# EdgeMax_ExtraMemory.net
KiCad netlist of a schematic drawn in Altium Designer
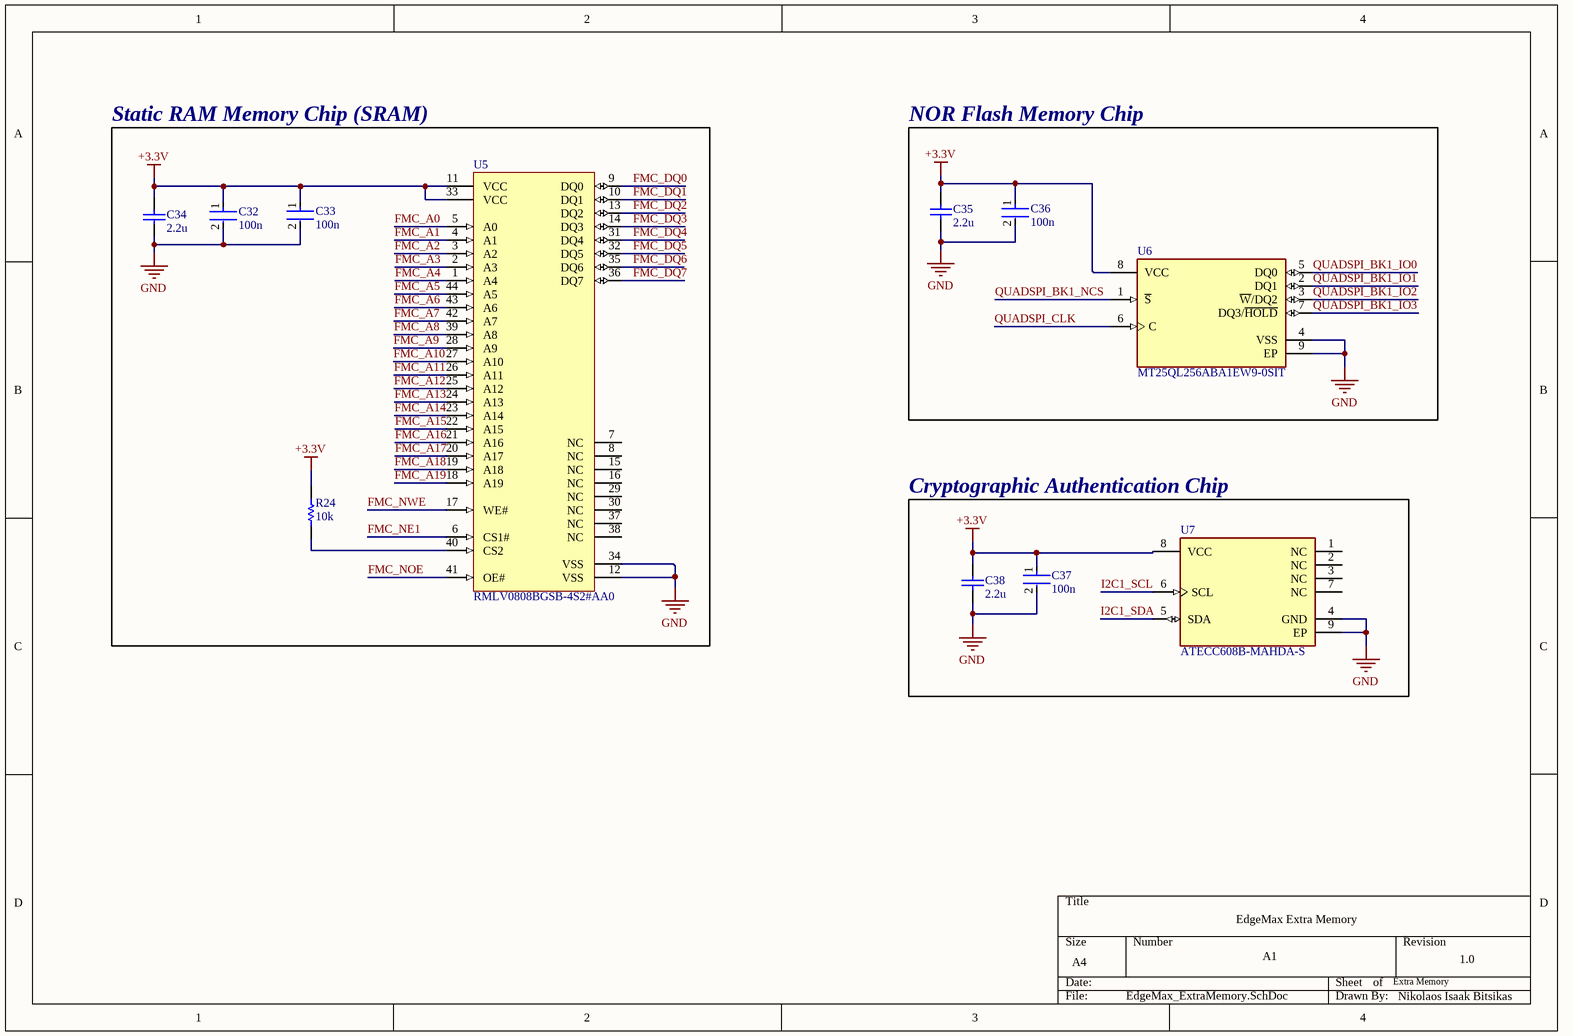
[diagram p0: EdgeMax_ExtraMemory.SchDoc]

(export (version "E")
  (design (tool "Eeschema 10.0.6"))
  (components
    (comp (ref "C32")
      (value "100n")
      (footprint "FP-CL10-IPC_A")
      (description "Cap Ceramic 100nF 50V X7R ±10% Pad SMD 0603 +125°C T/R")
      (fields (field (name "VOLTAGE") "50V") (field (name "TOLERANCE") "10%"))
      (libsource (lib "Altium Content Vault") (part "b4654b650e69147ec39a6b967a45e02"))
    )
    (comp (ref "C33")
      (value "100n")
      (footprint "FP-CL10-IPC_A")
      (description "Cap Ceramic 100nF 50V X7R ±10% Pad SMD 0603 +125°C T/R")
      (fields (field (name "VOLTAGE") "50V") (field (name "TOLERANCE") "10%"))
      (libsource (lib "Altium Content Vault") (part "b4654b650e69147ec39a6b967a45e02"))
    )
    (comp (ref "C34")
      (value "2.2u")
      (footprint "CAPC2013X135X50ML10T20")
      (fields (field (name "MANUFACTURER") "Murata") (field (name "PART NUMBER") "GRM21BR71C225KA12L"))
      (libsource (lib "Altium Content Vault") (part "CAP"))
    )
    (comp (ref "C35")
      (value "2.2u")
      (footprint "CAPC2013X135X50ML10T20")
      (fields (field (name "MANUFACTURER") "Murata") (field (name "PART NUMBER") "GRM21BR71C225KA12L"))
      (libsource (lib "Altium Content Vault") (part "CAP"))
    )
    (comp (ref "C36")
      (value "100n")
      (footprint "FP-CL10-IPC_A")
      (description "Cap Ceramic 100nF 50V X7R ±10% Pad SMD 0603 +125°C T/R")
      (fields (field (name "VOLTAGE") "50V") (field (name "TOLERANCE") "10%"))
      (libsource (lib "Altium Content Vault") (part "b4654b650e69147ec39a6b967a45e02"))
    )
    (comp (ref "C37")
      (value "100n")
      (footprint "FP-CL10-IPC_A")
      (description "Cap Ceramic 100nF 50V X7R ±10% Pad SMD 0603 +125°C T/R")
      (fields (field (name "VOLTAGE") "50V") (field (name "TOLERANCE") "10%"))
      (libsource (lib "Altium Content Vault") (part "b4654b650e69147ec39a6b967a45e02"))
    )
    (comp (ref "C38")
      (value "2.2u")
      (footprint "CAPC2013X135X50ML10T20")
      (fields (field (name "MANUFACTURER") "Murata") (field (name "PART NUMBER") "GRM21BR71C225KA12L"))
      (libsource (lib "Altium Content Vault") (part "CAP"))
    )
    (comp (ref "R24")
      (value "10k")
      (footprint "RESC2013X60X35NL10T20")
      (description "Chip Resistor, 10 KOhm, +/- 1%, 0.125 W, -55 to 155 degC, 0805 (2012 Metric), RoHS, Tape and Reel")
      (fields (field (name "MANUFACTURER") "Yageo"))
      (libsource (lib "Altium Content Vault") (part "RES-2"))
    )
    (comp (ref "U5")
      (value "RMLV0808BGSB-4S2#AA0")
      (footprint "TSOP80P1180X120_HS-45_PTSB0044GG-A_N")
      (description "SRAM Chip Async Single 3V 8M-Bit 1024K x 8 55ns 44-Pin TSOP-II Tray")
      (libsource (lib "Altium Content Vault") (part "5e764e3fbc5a59d1b6ce4e7e4f34d20"))
    )
    (comp (ref "U6")
      (value "MT25QL256ABA1EW9-0SIT")
      (footprint "FP-W9-IPC_C")
      (description "IC FLASH 256M SPI 133MHZ 8WPDFN")
      (fields
        (field (name "MANUFACTURER") "Micron")
        (field (name "OCTOPART") "https://octopart.com/mt25ql256aba1ew9-0sit-micron-48615906")
      )
      (libsource (lib "Altium Content Vault") (part "3463bc91256e0a3fe8a17a782a29a2f"))
    )
    (comp (ref "U7")
      (value "ATECC608B-MAHDA-S")
      (footprint "FP-C04-21355-Q4B-IPC_B")
      (description "IC AUTHENTICATION CHIP")
      (libsource (lib "Altium Content Vault") (part "86edb8706b822f0bad86d9b788e16ff"))
    )
  )
  (nets
    (net (code "1") (name "+3.3V") (class "Default")
      (node (ref "C32") (pin "1") (pinfunction "1_1") (pintype "passive"))
      (node (ref "C33") (pin "1") (pinfunction "1_1") (pintype "passive"))
      (node (ref "C34") (pin "2") (pinfunction "2_2") (pintype "passive"))
      (node (ref "C35") (pin "2") (pinfunction "2_2") (pintype "passive"))
      (node (ref "C36") (pin "1") (pinfunction "1_1") (pintype "passive"))
      (node (ref "C37") (pin "1") (pinfunction "1_1") (pintype "passive"))
      (node (ref "C38") (pin "2") (pinfunction "2_2") (pintype "passive"))
      (node (ref "R24") (pin "2") (pinfunction "2_2") (pintype "passive"))
      (node (ref "U5") (pin "11") (pinfunction "VCC_11") (pintype "power_in"))
      (node (ref "U5") (pin "33") (pinfunction "VCC_33") (pintype "power_in"))
      (node (ref "U6") (pin "8") (pinfunction "VCC_8") (pintype "power_in"))
      (node (ref "U7") (pin "8") (pinfunction "VCC_8") (pintype "power_in"))
    )
    (net (code "2") (name "/FMC_A0") (class "Default")
      (node (ref "U5") (pin "5") (pinfunction "A0_5") (pintype "input"))
    )
    (net (code "3") (name "/FMC_A1") (class "Default")
      (node (ref "U5") (pin "4") (pinfunction "A1_4") (pintype "input"))
    )
    (net (code "4") (name "/FMC_A2") (class "Default")
      (node (ref "U5") (pin "3") (pinfunction "A2_3") (pintype "input"))
    )
    (net (code "5") (name "/FMC_A3") (class "Default")
      (node (ref "U5") (pin "2") (pinfunction "A3_2") (pintype "input"))
    )
    (net (code "6") (name "/FMC_A4") (class "Default")
      (node (ref "U5") (pin "1") (pinfunction "A4_1") (pintype "input"))
    )
    (net (code "7") (name "/FMC_A5") (class "Default")
      (node (ref "U5") (pin "44") (pinfunction "A5_44") (pintype "input"))
    )
    (net (code "8") (name "/FMC_A6") (class "Default")
      (node (ref "U5") (pin "43") (pinfunction "A6_43") (pintype "input"))
    )
    (net (code "9") (name "/FMC_A7") (class "Default")
      (node (ref "U5") (pin "42") (pinfunction "A7_42") (pintype "input"))
    )
    (net (code "10") (name "/FMC_A8") (class "Default")
      (node (ref "U5") (pin "39") (pinfunction "A8_39") (pintype "input"))
    )
    (net (code "11") (name "/FMC_A9") (class "Default")
      (node (ref "U5") (pin "28") (pinfunction "A9_28") (pintype "input"))
    )
    (net (code "12") (name "/FMC_A10") (class "Default")
      (node (ref "U5") (pin "27") (pinfunction "A10_27") (pintype "input"))
    )
    (net (code "13") (name "/FMC_A11") (class "Default")
      (node (ref "U5") (pin "26") (pinfunction "A11_26") (pintype "input"))
    )
    (net (code "14") (name "/FMC_A12") (class "Default")
      (node (ref "U5") (pin "25") (pinfunction "A12_25") (pintype "input"))
    )
    (net (code "15") (name "/FMC_A13") (class "Default")
      (node (ref "U5") (pin "24") (pinfunction "A13_24") (pintype "input"))
    )
    (net (code "16") (name "/FMC_A14") (class "Default")
      (node (ref "U5") (pin "23") (pinfunction "A14_23") (pintype "input"))
    )
    (net (code "17") (name "/FMC_A15") (class "Default")
      (node (ref "U5") (pin "22") (pinfunction "A15_22") (pintype "input"))
    )
    (net (code "18") (name "/FMC_A16") (class "Default")
      (node (ref "U5") (pin "21") (pinfunction "A16_21") (pintype "input"))
    )
    (net (code "19") (name "/FMC_A17") (class "Default")
      (node (ref "U5") (pin "20") (pinfunction "A17_20") (pintype "input"))
    )
    (net (code "20") (name "/FMC_A18") (class "Default")
      (node (ref "U5") (pin "19") (pinfunction "A18_19") (pintype "input"))
    )
    (net (code "21") (name "/FMC_A19") (class "Default")
      (node (ref "U5") (pin "18") (pinfunction "A19_18") (pintype "input"))
    )
    (net (code "22") (name "/FMC_DQ0") (class "Default")
      (node (ref "U5") (pin "9") (pinfunction "DQ0_9") (pintype "bidirectional"))
    )
    (net (code "23") (name "/FMC_DQ1") (class "Default")
      (node (ref "U5") (pin "10") (pinfunction "DQ1_10") (pintype "bidirectional"))
    )
    (net (code "24") (name "/FMC_DQ2") (class "Default")
      (node (ref "U5") (pin "13") (pinfunction "DQ2_13") (pintype "bidirectional"))
    )
    (net (code "25") (name "/FMC_DQ3") (class "Default")
      (node (ref "U5") (pin "14") (pinfunction "DQ3_14") (pintype "bidirectional"))
    )
    (net (code "26") (name "/FMC_DQ4") (class "Default")
      (node (ref "U5") (pin "31") (pinfunction "DQ4_31") (pintype "bidirectional"))
    )
    (net (code "27") (name "/FMC_DQ5") (class "Default")
      (node (ref "U5") (pin "32") (pinfunction "DQ5_32") (pintype "bidirectional"))
    )
    (net (code "28") (name "/FMC_DQ6") (class "Default")
      (node (ref "U5") (pin "35") (pinfunction "DQ6_35") (pintype "bidirectional"))
    )
    (net (code "29") (name "/FMC_DQ7") (class "Default")
      (node (ref "U5") (pin "36") (pinfunction "DQ7_36") (pintype "bidirectional"))
    )
    (net (code "30") (name "/FMC_NOE") (class "Default")
      (node (ref "U5") (pin "41") (pinfunction "OE#_41") (pintype "input"))
    )
    (net (code "31") (name "/FMC_NWE") (class "Default")
      (node (ref "U5") (pin "17") (pinfunction "WE#_17") (pintype "input"))
    )
    (net (code "32") (name "/FMC_ΝΕ1") (class "Default")
      (node (ref "U5") (pin "6") (pinfunction "CS1#_6") (pintype "input"))
    )
    (net (code "33") (name "/I2C1_SCL") (class "Default")
      (node (ref "U7") (pin "6") (pinfunction "SCL_6") (pintype "input"))
    )
    (net (code "34") (name "/I2C1_SDA") (class "Default")
      (node (ref "U7") (pin "5") (pinfunction "SDA_5") (pintype "bidirectional"))
    )
    (net (code "35") (name "/QUADSPI_BK1_IO0") (class "Default")
      (node (ref "U6") (pin "5") (pinfunction "DQ0_5") (pintype "bidirectional"))
    )
    (net (code "36") (name "/QUADSPI_BK1_IO1") (class "Default")
      (node (ref "U6") (pin "2") (pinfunction "DQ1_2") (pintype "bidirectional"))
    )
    (net (code "37") (name "/QUADSPI_BK1_IO2") (class "Default")
      (node (ref "U6") (pin "3") (pinfunction "~{W}/DQ2_3") (pintype "bidirectional"))
    )
    (net (code "38") (name "/QUADSPI_BK1_IO3") (class "Default")
      (node (ref "U6") (pin "7") (pinfunction "DQ3/~{HOLD}_7") (pintype "bidirectional"))
    )
    (net (code "39") (name "/QUADSPI_BK1_NCS") (class "Default")
      (node (ref "U6") (pin "1") (pinfunction "~{S}_1") (pintype "input"))
    )
    (net (code "40") (name "/QUADSPI_CLK") (class "Default")
      (node (ref "U6") (pin "6") (pinfunction "C_6") (pintype "input"))
    )
    (net (code "41") (name "GND") (class "Default")
      (node (ref "C32") (pin "2") (pinfunction "2_2") (pintype "passive"))
      (node (ref "C33") (pin "2") (pinfunction "2_2") (pintype "passive"))
      (node (ref "C34") (pin "1") (pinfunction "1_1") (pintype "passive"))
      (node (ref "C35") (pin "1") (pinfunction "1_1") (pintype "passive"))
      (node (ref "C36") (pin "2") (pinfunction "2_2") (pintype "passive"))
      (node (ref "C37") (pin "2") (pinfunction "2_2") (pintype "passive"))
      (node (ref "C38") (pin "1") (pinfunction "1_1") (pintype "passive"))
      (node (ref "U5") (pin "12") (pinfunction "VSS_12") (pintype "power_in"))
      (node (ref "U5") (pin "34") (pinfunction "VSS_34") (pintype "power_in"))
      (node (ref "U6") (pin "4") (pinfunction "VSS_4") (pintype "power_in"))
      (node (ref "U6") (pin "9") (pinfunction "EP_9") (pintype "power_in"))
      (node (ref "U7") (pin "4") (pinfunction "GND_4") (pintype "power_in"))
      (node (ref "U7") (pin "9") (pinfunction "EP_9") (pintype "passive"))
    )
    (net (code "42") (name "Net-(U5-CS2)") (class "Default")
      (node (ref "R24") (pin "1") (pinfunction "1_1") (pintype "passive"))
      (node (ref "U5") (pin "40") (pinfunction "CS2_40") (pintype "input"))
    )
    (net (code "43") (name "unconnected-(U5-NC-Pad7)") (class "Default")
      (node (ref "U5") (pin "7") (pinfunction "NC_7") (pintype "passive"))
    )
    (net (code "44") (name "unconnected-(U5-NC-Pad8)") (class "Default")
      (node (ref "U5") (pin "8") (pinfunction "NC_8") (pintype "passive"))
    )
    (net (code "45") (name "unconnected-(U5-NC-Pad15)") (class "Default")
      (node (ref "U5") (pin "15") (pinfunction "NC_15") (pintype "passive"))
    )
    (net (code "46") (name "unconnected-(U5-NC-Pad16)") (class "Default")
      (node (ref "U5") (pin "16") (pinfunction "NC_16") (pintype "passive"))
    )
    (net (code "47") (name "unconnected-(U5-NC-Pad29)") (class "Default")
      (node (ref "U5") (pin "29") (pinfunction "NC_29") (pintype "passive"))
    )
    (net (code "48") (name "unconnected-(U5-NC-Pad30)") (class "Default")
      (node (ref "U5") (pin "30") (pinfunction "NC_30") (pintype "passive"))
    )
    (net (code "49") (name "unconnected-(U5-NC-Pad37)") (class "Default")
      (node (ref "U5") (pin "37") (pinfunction "NC_37") (pintype "passive"))
    )
    (net (code "50") (name "unconnected-(U5-NC-Pad38)") (class "Default")
      (node (ref "U5") (pin "38") (pinfunction "NC_38") (pintype "passive"))
    )
    (net (code "51") (name "unconnected-(U7-NC-Pad1)") (class "Default")
      (node (ref "U7") (pin "1") (pinfunction "NC_1") (pintype "passive"))
    )
    (net (code "52") (name "unconnected-(U7-NC-Pad2)") (class "Default")
      (node (ref "U7") (pin "2") (pinfunction "NC_2") (pintype "passive"))
    )
    (net (code "53") (name "unconnected-(U7-NC-Pad3)") (class "Default")
      (node (ref "U7") (pin "3") (pinfunction "NC_3") (pintype "passive"))
    )
    (net (code "54") (name "unconnected-(U7-NC-Pad7)") (class "Default")
      (node (ref "U7") (pin "7") (pinfunction "NC_7") (pintype "passive"))
    )
  )
)
